# Auxillary_Supply_Break_Out.net
KiCad netlist of a schematic drawn in Altium Designer
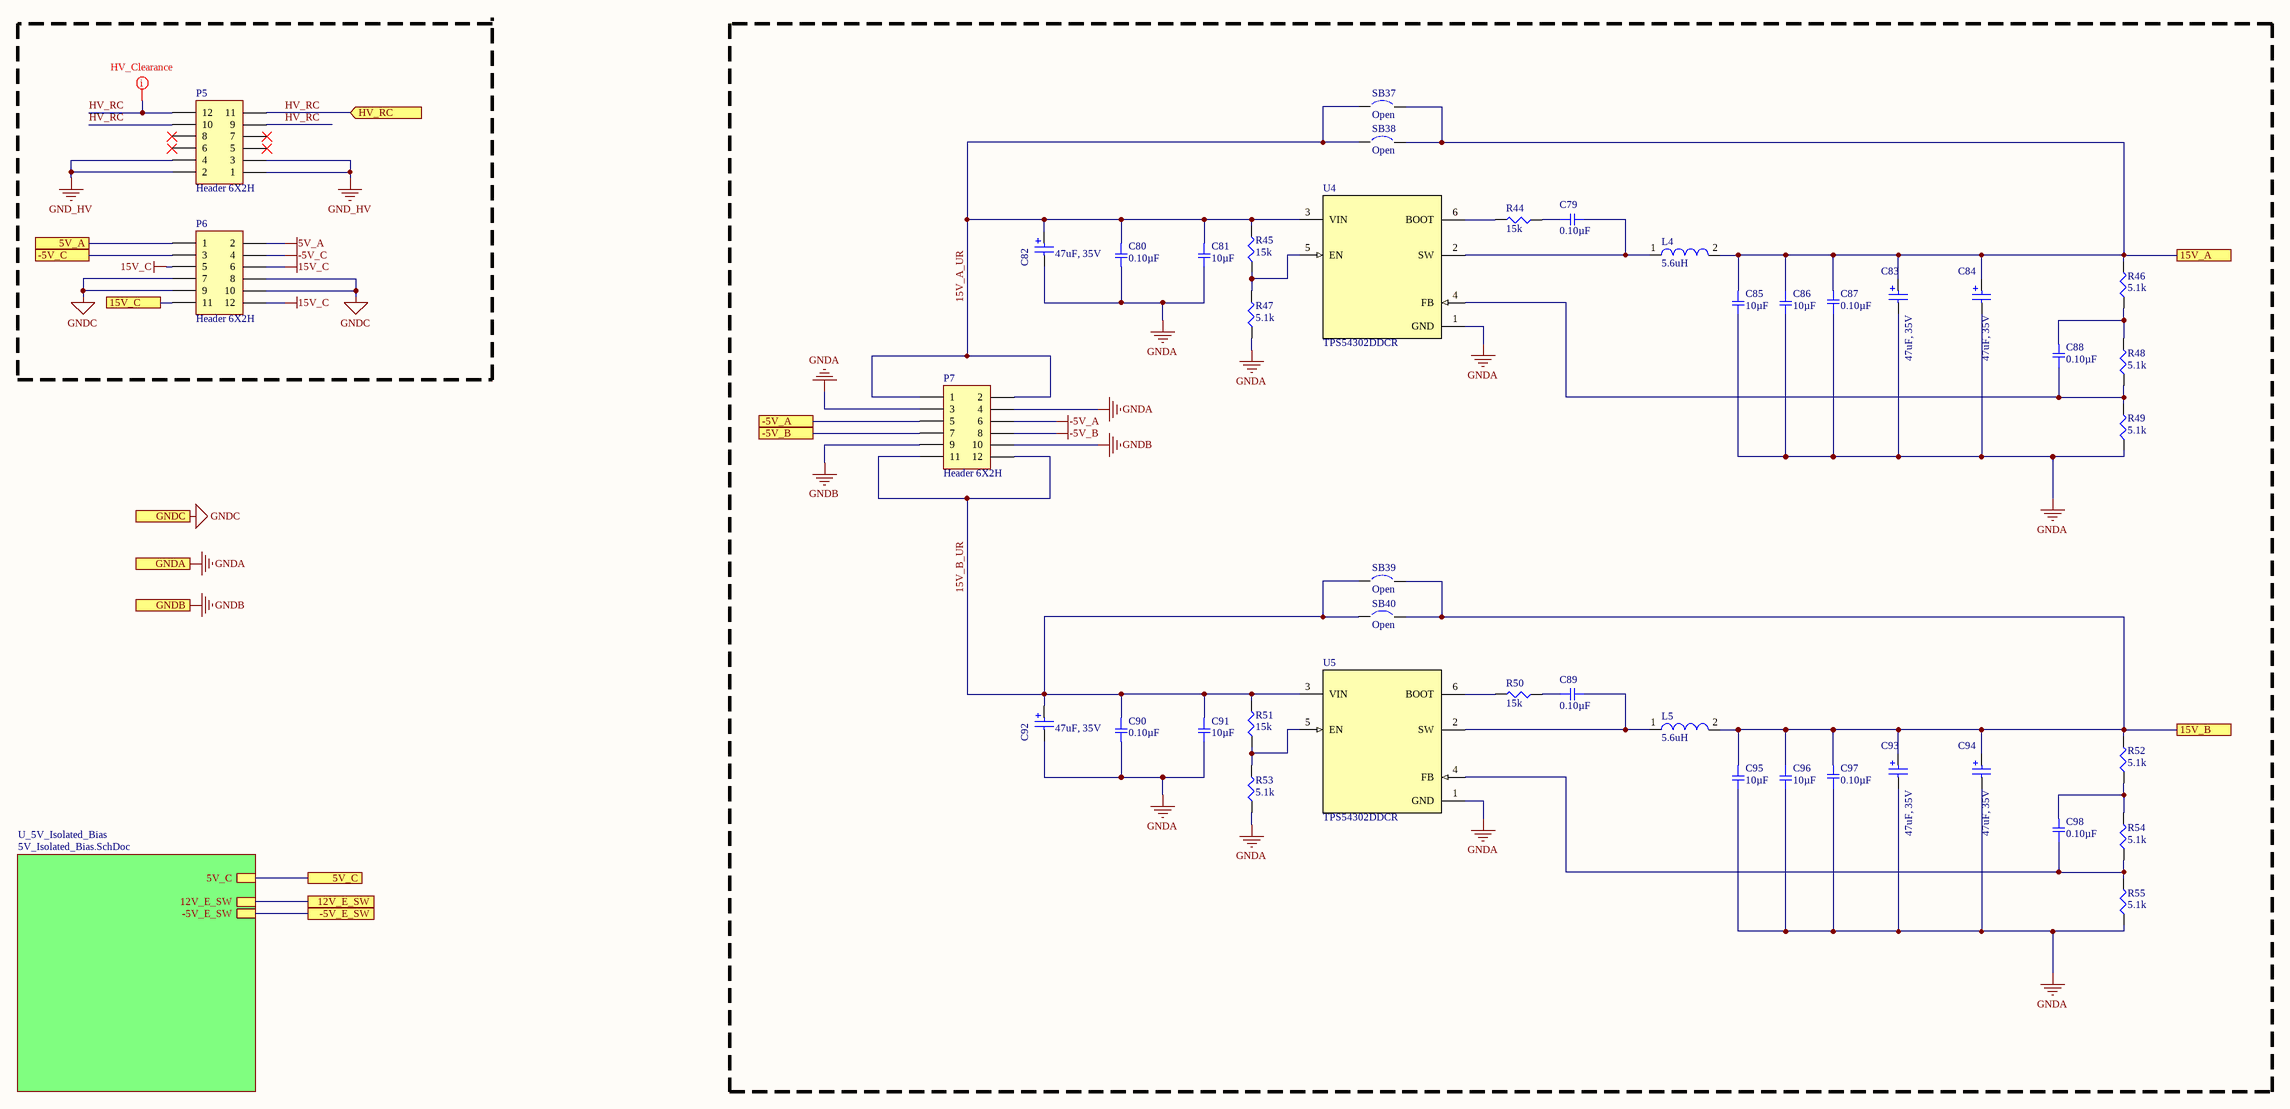
[diagram p0: Auxillary Supply Break Out.SchDoc]

(export (version "E")
  (design (tool "Eeschema 10.0.6"))
  (components
    (comp (ref "C79")
      (value "0.10µF")
      (footprint "SMD-0805C")
      (description "CAP CER 0.1UF 50V X7R 0805")
      (fields
        (field (name "DIGI-KEY PART NUMBER") "490-11955-1-ND")
        (field (name "PART NUMBER") "GCD21BR71H104KA01L")
      )
      (libsource (lib "capacitor_murata_0805") (part "GCD21BR71H104KA01L"))
    )
    (comp (ref "C80")
      (value "0.10µF")
      (footprint "SMD-0805C")
      (description "CAP CER 0.1UF 50V X7R 0805")
      (fields
        (field (name "DIGI-KEY PART NUMBER") "490-11955-1-ND")
        (field (name "PART NUMBER") "GCD21BR71H104KA01L")
      )
      (libsource (lib "capacitor_murata_0805") (part "GCD21BR71H104KA01L"))
    )
    (comp (ref "C81")
      (value "10µF")
      (footprint "SMD-0805C")
      (description "CAP CER 10UF 25V X5R 0805")
      (fields
        (field (name "DIGI-KEY PART NUMBER") "490-7207-1-ND")
        (field (name "PART NUMBER") "GRM219R61E106KA12D")
      )
      (libsource (lib "capacitor_murata_0805") (part "GRM219R61E106KA12D"))
    )
    (comp (ref "C82")
      (value "47uF, 35V")
      (footprint "WCAP-ASLU_6.3x7.7")
      (description "WCAP-ASLU Aluminium Electrolytic Capacitors, D6.3mm x L7.7mm, 47uF, +/-20%, 35VDC")
      (fields (field (name "PART NUMBER") "865090545008") (field (name "PUBLISHER") "Wurth Elektronik"))
      (libsource (lib "Altium_WCAP-ASLU_SMD") (part "865090545008"))
    )
    (comp (ref "C83")
      (value "47uF, 35V")
      (footprint "WCAP-ASLU_6.3x7.7")
      (description "WCAP-ASLU Aluminium Electrolytic Capacitors, D6.3mm x L7.7mm, 47uF, +/-20%, 35VDC")
      (fields (field (name "PART NUMBER") "865090545008") (field (name "PUBLISHER") "Wurth Elektronik"))
      (libsource (lib "Altium_WCAP-ASLU_SMD") (part "865090545008"))
    )
    (comp (ref "C84")
      (value "47uF, 35V")
      (footprint "WCAP-ASLU_6.3x7.7")
      (description "WCAP-ASLU Aluminium Electrolytic Capacitors, D6.3mm x L7.7mm, 47uF, +/-20%, 35VDC")
      (fields (field (name "PART NUMBER") "865090545008") (field (name "PUBLISHER") "Wurth Elektronik"))
      (libsource (lib "Altium_WCAP-ASLU_SMD") (part "865090545008"))
    )
    (comp (ref "C85")
      (value "10µF")
      (footprint "SMD-0805C")
      (description "CAP CER 10UF 25V X5R 0805")
      (fields
        (field (name "DIGI-KEY PART NUMBER") "490-7207-1-ND")
        (field (name "PART NUMBER") "GRM219R61E106KA12D")
      )
      (libsource (lib "capacitor_murata_0805") (part "GRM219R61E106KA12D"))
    )
    (comp (ref "C86")
      (value "10µF")
      (footprint "SMD-0805C")
      (description "CAP CER 10UF 25V X5R 0805")
      (fields
        (field (name "DIGI-KEY PART NUMBER") "490-7207-1-ND")
        (field (name "PART NUMBER") "GRM219R61E106KA12D")
      )
      (libsource (lib "capacitor_murata_0805") (part "GRM219R61E106KA12D"))
    )
    (comp (ref "C87")
      (value "0.10µF")
      (footprint "SMD-0805C")
      (description "CAP CER 0.1UF 50V X7R 0805")
      (fields
        (field (name "DIGI-KEY PART NUMBER") "490-11955-1-ND")
        (field (name "PART NUMBER") "GCD21BR71H104KA01L")
      )
      (libsource (lib "capacitor_murata_0805") (part "GCD21BR71H104KA01L"))
    )
    (comp (ref "C88")
      (value "0.10µF")
      (footprint "SMD-0805C")
      (description "CAP CER 0.1UF 50V X7R 0805")
      (fields
        (field (name "DIGI-KEY PART NUMBER") "490-11955-1-ND")
        (field (name "PART NUMBER") "GCD21BR71H104KA01L")
      )
      (libsource (lib "capacitor_murata_0805") (part "GCD21BR71H104KA01L"))
    )
    (comp (ref "C89")
      (value "0.10µF")
      (footprint "SMD-0805C")
      (description "CAP CER 0.1UF 50V X7R 0805")
      (fields
        (field (name "DIGI-KEY PART NUMBER") "490-11955-1-ND")
        (field (name "PART NUMBER") "GCD21BR71H104KA01L")
      )
      (libsource (lib "capacitor_murata_0805") (part "GCD21BR71H104KA01L"))
    )
    (comp (ref "C90")
      (value "0.10µF")
      (footprint "SMD-0805C")
      (description "CAP CER 0.1UF 50V X7R 0805")
      (fields
        (field (name "DIGI-KEY PART NUMBER") "490-11955-1-ND")
        (field (name "PART NUMBER") "GCD21BR71H104KA01L")
      )
      (libsource (lib "capacitor_murata_0805") (part "GCD21BR71H104KA01L"))
    )
    (comp (ref "C91")
      (value "10µF")
      (footprint "SMD-0805C")
      (description "CAP CER 10UF 25V X5R 0805")
      (fields
        (field (name "DIGI-KEY PART NUMBER") "490-7207-1-ND")
        (field (name "PART NUMBER") "GRM219R61E106KA12D")
      )
      (libsource (lib "capacitor_murata_0805") (part "GRM219R61E106KA12D"))
    )
    (comp (ref "C92")
      (value "47uF, 35V")
      (footprint "WCAP-ASLU_6.3x7.7")
      (description "WCAP-ASLU Aluminium Electrolytic Capacitors, D6.3mm x L7.7mm, 47uF, +/-20%, 35VDC")
      (fields (field (name "PART NUMBER") "865090545008") (field (name "PUBLISHER") "Wurth Elektronik"))
      (libsource (lib "Altium_WCAP-ASLU_SMD") (part "865090545008"))
    )
    (comp (ref "C93")
      (value "47uF, 35V")
      (footprint "WCAP-ASLU_6.3x7.7")
      (description "WCAP-ASLU Aluminium Electrolytic Capacitors, D6.3mm x L7.7mm, 47uF, +/-20%, 35VDC")
      (fields (field (name "PART NUMBER") "865090545008") (field (name "PUBLISHER") "Wurth Elektronik"))
      (libsource (lib "Altium_WCAP-ASLU_SMD") (part "865090545008"))
    )
    (comp (ref "C94")
      (value "47uF, 35V")
      (footprint "WCAP-ASLU_6.3x7.7")
      (description "WCAP-ASLU Aluminium Electrolytic Capacitors, D6.3mm x L7.7mm, 47uF, +/-20%, 35VDC")
      (fields (field (name "PART NUMBER") "865090545008") (field (name "PUBLISHER") "Wurth Elektronik"))
      (libsource (lib "Altium_WCAP-ASLU_SMD") (part "865090545008"))
    )
    (comp (ref "C95")
      (value "10µF")
      (footprint "SMD-0805C")
      (description "CAP CER 10UF 25V X5R 0805")
      (fields
        (field (name "DIGI-KEY PART NUMBER") "490-7207-1-ND")
        (field (name "PART NUMBER") "GRM219R61E106KA12D")
      )
      (libsource (lib "capacitor_murata_0805") (part "GRM219R61E106KA12D"))
    )
    (comp (ref "C96")
      (value "10µF")
      (footprint "SMD-0805C")
      (description "CAP CER 10UF 25V X5R 0805")
      (fields
        (field (name "DIGI-KEY PART NUMBER") "490-7207-1-ND")
        (field (name "PART NUMBER") "GRM219R61E106KA12D")
      )
      (libsource (lib "capacitor_murata_0805") (part "GRM219R61E106KA12D"))
    )
    (comp (ref "C97")
      (value "0.10µF")
      (footprint "SMD-0805C")
      (description "CAP CER 0.1UF 50V X7R 0805")
      (fields
        (field (name "DIGI-KEY PART NUMBER") "490-11955-1-ND")
        (field (name "PART NUMBER") "GCD21BR71H104KA01L")
      )
      (libsource (lib "capacitor_murata_0805") (part "GCD21BR71H104KA01L"))
    )
    (comp (ref "C98")
      (value "0.10µF")
      (footprint "SMD-0805C")
      (description "CAP CER 0.1UF 50V X7R 0805")
      (fields
        (field (name "DIGI-KEY PART NUMBER") "490-11955-1-ND")
        (field (name "PART NUMBER") "GCD21BR71H104KA01L")
      )
      (libsource (lib "capacitor_murata_0805") (part "GCD21BR71H104KA01L"))
    )
    (comp (ref "L4")
      (value "5.6uH")
      (footprint "WE-PD-L")
      (description "SMD-Shielded Power Inductor WE-PD, L = 4.70 µH")
      (libsource (lib "Altium Content Vault") (part "PAS-IND-INDUCTOR-2"))
    )
    (comp (ref "L5")
      (value "5.6uH")
      (footprint "WE-PD-L")
      (description "SMD-Shielded Power Inductor WE-PD, L = 4.70 µH")
      (libsource (lib "Altium Content Vault") (part "PAS-IND-INDUCTOR-2"))
    )
    (comp (ref "P5")
      (value "Header 6X2H")
      (footprint "Stackable-Conn")
      (description "Header, 6-Pin, Dual row, Right Angle")
      (fields (field (name "PUBLISHER") "Altium Limited"))
      (libsource (lib "") (part "Header 6X2H_1"))
    )
    (comp (ref "P6")
      (value "Header 6X2H")
      (footprint "Stackable-Conn")
      (description "Header, 6-Pin, Dual row, Right Angle")
      (fields (field (name "PUBLISHER") "Altium Limited"))
      (libsource (lib "Power Board UCC28951") (part "Header 6X2H"))
    )
    (comp (ref "P7")
      (value "Header 6X2H")
      (footprint "Stackable-Conn")
      (description "Header, 6-Pin, Dual row, Right Angle")
      (fields (field (name "PUBLISHER") "Altium Limited"))
      (libsource (lib "Power Board UCC28951") (part "Header 6X2H"))
    )
    (comp (ref "R44")
      (value "15k")
      (footprint "SMD-0603-RES")
      (description "RES SMD 15K OHM 1% 1/10W 0603")
      (fields
        (field (name "PART NUMBER") "ERJ-3EKF1502V")
        (field (name "DIGI-KEY PART NUMBER") "P15.0KHCT-ND")
      )
      (libsource (lib "Panasonic_ERJ_0603") (part "ERJ-3EKF1502V"))
    )
    (comp (ref "R45")
      (value "15k")
      (footprint "SMD-0603-RES")
      (description "RES SMD 15K OHM 1% 1/10W 0603")
      (fields
        (field (name "PART NUMBER") "ERJ-3EKF1502V")
        (field (name "DIGI-KEY PART NUMBER") "P15.0KHCT-ND")
      )
      (libsource (lib "Panasonic_ERJ_0603") (part "ERJ-3EKF1502V"))
    )
    (comp (ref "R46")
      (value "5.1k")
      (footprint "SMD-0603-RES")
      (description "RES SMD 5.1K OHM 1% 1/10W 0603")
      (fields
        (field (name "PART NUMBER") "ERJ-3EKF5101V")
        (field (name "DIGI-KEY PART NUMBER") "P5.10KHCT-ND")
      )
      (libsource (lib "Panasonic_ERJ_0603") (part "ERJ-3EKF5101V"))
    )
    (comp (ref "R47")
      (value "5.1k")
      (footprint "SMD-0603-RES")
      (description "RES SMD 5.1K OHM 1% 1/10W 0603")
      (fields
        (field (name "PART NUMBER") "ERJ-3EKF5101V")
        (field (name "DIGI-KEY PART NUMBER") "P5.10KHCT-ND")
      )
      (libsource (lib "Panasonic_ERJ_0603") (part "ERJ-3EKF5101V"))
    )
    (comp (ref "R48")
      (value "5.1k")
      (footprint "SMD-0603-RES")
      (description "RES SMD 5.1K OHM 1% 1/10W 0603")
      (fields
        (field (name "PART NUMBER") "ERJ-3EKF5101V")
        (field (name "DIGI-KEY PART NUMBER") "P5.10KHCT-ND")
      )
      (libsource (lib "Panasonic_ERJ_0603") (part "ERJ-3EKF5101V"))
    )
    (comp (ref "R49")
      (value "5.1k")
      (footprint "SMD-0603-RES")
      (description "RES SMD 5.1K OHM 1% 1/10W 0603")
      (fields
        (field (name "PART NUMBER") "ERJ-3EKF5101V")
        (field (name "DIGI-KEY PART NUMBER") "P5.10KHCT-ND")
      )
      (libsource (lib "Panasonic_ERJ_0603") (part "ERJ-3EKF5101V"))
    )
    (comp (ref "R50")
      (value "15k")
      (footprint "SMD-0603-RES")
      (description "RES SMD 15K OHM 1% 1/10W 0603")
      (fields
        (field (name "PART NUMBER") "ERJ-3EKF1502V")
        (field (name "DIGI-KEY PART NUMBER") "P15.0KHCT-ND")
      )
      (libsource (lib "Panasonic_ERJ_0603") (part "ERJ-3EKF1502V"))
    )
    (comp (ref "R51")
      (value "15k")
      (footprint "SMD-0603-RES")
      (description "RES SMD 15K OHM 1% 1/10W 0603")
      (fields
        (field (name "PART NUMBER") "ERJ-3EKF1502V")
        (field (name "DIGI-KEY PART NUMBER") "P15.0KHCT-ND")
      )
      (libsource (lib "Panasonic_ERJ_0603") (part "ERJ-3EKF1502V"))
    )
    (comp (ref "R52")
      (value "5.1k")
      (footprint "SMD-0603-RES")
      (description "RES SMD 5.1K OHM 1% 1/10W 0603")
      (fields
        (field (name "PART NUMBER") "ERJ-3EKF5101V")
        (field (name "DIGI-KEY PART NUMBER") "P5.10KHCT-ND")
      )
      (libsource (lib "Panasonic_ERJ_0603") (part "ERJ-3EKF5101V"))
    )
    (comp (ref "R53")
      (value "5.1k")
      (footprint "SMD-0603-RES")
      (description "RES SMD 5.1K OHM 1% 1/10W 0603")
      (fields
        (field (name "PART NUMBER") "ERJ-3EKF5101V")
        (field (name "DIGI-KEY PART NUMBER") "P5.10KHCT-ND")
      )
      (libsource (lib "Panasonic_ERJ_0603") (part "ERJ-3EKF5101V"))
    )
    (comp (ref "R54")
      (value "5.1k")
      (footprint "SMD-0603-RES")
      (description "RES SMD 5.1K OHM 1% 1/10W 0603")
      (fields
        (field (name "PART NUMBER") "ERJ-3EKF5101V")
        (field (name "DIGI-KEY PART NUMBER") "P5.10KHCT-ND")
      )
      (libsource (lib "Panasonic_ERJ_0603") (part "ERJ-3EKF5101V"))
    )
    (comp (ref "R55")
      (value "5.1k")
      (footprint "SMD-0603-RES")
      (description "RES SMD 5.1K OHM 1% 1/10W 0603")
      (fields
        (field (name "PART NUMBER") "ERJ-3EKF5101V")
        (field (name "DIGI-KEY PART NUMBER") "P5.10KHCT-ND")
      )
      (libsource (lib "Panasonic_ERJ_0603") (part "ERJ-3EKF5101V"))
    )
    (comp (ref "SB37")
      (value "Open")
      (footprint "Solder Bridge - HP")
      (description "Circuit Breaker")
      (fields (field (name "PUBLISHER") "Altium Limited"))
      (libsource (lib "Power Board UCC28951") (part "Solder Bridge"))
    )
    (comp (ref "SB38")
      (value "Open")
      (footprint "Solder Bridge - HP")
      (description "Circuit Breaker")
      (fields (field (name "PUBLISHER") "Altium Limited"))
      (libsource (lib "Power Board UCC28951") (part "Solder Bridge"))
    )
    (comp (ref "SB39")
      (value "Open")
      (footprint "Solder Bridge - HP")
      (description "Circuit Breaker")
      (fields (field (name "PUBLISHER") "Altium Limited"))
      (libsource (lib "Power Board UCC28951") (part "Solder Bridge"))
    )
    (comp (ref "SB40")
      (value "Open")
      (footprint "Solder Bridge - HP")
      (description "Circuit Breaker")
      (fields (field (name "PUBLISHER") "Altium Limited"))
      (libsource (lib "Power Board UCC28951") (part "Solder Bridge"))
    )
    (comp (ref "U4")
      (value "TPS54302DDCR")
      (footprint "SOT95P278X110-6N")
      (description "Imported")
      (fields (field (name "PARTNUMBER") "TPS54302DDC") (field (name "MANUFACTURER") "Texas Instruments"))
      (libsource (lib "Power Board UCC28951") (part "TPS54302DDCR"))
    )
    (comp (ref "U5")
      (value "TPS54302DDCR")
      (footprint "SOT95P278X110-6N")
      (description "Imported")
      (fields (field (name "PARTNUMBER") "TPS54302DDC") (field (name "MANUFACTURER") "Texas Instruments"))
      (libsource (lib "Power Board UCC28951") (part "TPS54302DDCR"))
    )
  )
  (nets
    (net (code "1") (name "-5V_A") (class "Default")
      (node (ref "P7") (pin "5") (pinfunction "5_5") (pintype "passive"))
      (node (ref "P7") (pin "6") (pinfunction "6_6") (pintype "passive"))
    )
    (net (code "2") (name "-5V_B") (class "Default")
      (node (ref "P7") (pin "7") (pinfunction "7_7") (pintype "passive"))
      (node (ref "P7") (pin "8") (pinfunction "8_8") (pintype "passive"))
    )
    (net (code "3") (name "-5V_C") (class "Default")
      (node (ref "P6") (pin "3") (pinfunction "3_3") (pintype "passive"))
      (node (ref "P6") (pin "4") (pinfunction "4_4") (pintype "passive"))
    )
    (net (code "7") (name "/15V_A") (class "Default")
      (node (ref "C83") (pin "2") (pinfunction "P_2") (pintype "passive"))
      (node (ref "C84") (pin "2") (pinfunction "P_2") (pintype "passive"))
      (node (ref "C85") (pin "1") (pinfunction "1_1") (pintype "passive"))
      (node (ref "C86") (pin "1") (pinfunction "1_1") (pintype "passive"))
      (node (ref "C87") (pin "2") (pinfunction "2_2") (pintype "passive"))
      (node (ref "L4") (pin "2") (pinfunction "2_2") (pintype "passive"))
      (node (ref "R46") (pin "2") (pinfunction "2_2") (pintype "passive"))
      (node (ref "SB37") (pin "2") (pinfunction "2_2") (pintype "passive"))
      (node (ref "SB38") (pin "2") (pinfunction "2_2") (pintype "passive"))
    )
    (net (code "8") (name "/15V_A_UR") (class "Default")
      (node (ref "C80") (pin "1") (pinfunction "1_1") (pintype "passive"))
      (node (ref "C81") (pin "1") (pinfunction "1_1") (pintype "passive"))
      (node (ref "C82") (pin "2") (pinfunction "P_2") (pintype "passive"))
      (node (ref "P7") (pin "1") (pinfunction "1_1") (pintype "passive"))
      (node (ref "P7") (pin "2") (pinfunction "2_2") (pintype "passive"))
      (node (ref "R45") (pin "2") (pinfunction "2_2") (pintype "passive"))
      (node (ref "SB37") (pin "1") (pinfunction "1_1") (pintype "passive"))
      (node (ref "SB38") (pin "1") (pinfunction "1_1") (pintype "passive"))
      (node (ref "U4") (pin "3") (pinfunction "VIN_3") (pintype "power_in"))
    )
    (net (code "9") (name "/15V_B") (class "Default")
      (node (ref "C93") (pin "2") (pinfunction "P_2") (pintype "passive"))
      (node (ref "C94") (pin "2") (pinfunction "P_2") (pintype "passive"))
      (node (ref "C95") (pin "1") (pinfunction "1_1") (pintype "passive"))
      (node (ref "C96") (pin "1") (pinfunction "1_1") (pintype "passive"))
      (node (ref "C97") (pin "2") (pinfunction "2_2") (pintype "passive"))
      (node (ref "L5") (pin "2") (pinfunction "2_2") (pintype "passive"))
      (node (ref "R52") (pin "2") (pinfunction "2_2") (pintype "passive"))
      (node (ref "SB39") (pin "2") (pinfunction "2_2") (pintype "passive"))
      (node (ref "SB40") (pin "2") (pinfunction "2_2") (pintype "passive"))
    )
    (net (code "10") (name "/15V_B_UR") (class "Default")
      (node (ref "C90") (pin "1") (pinfunction "1_1") (pintype "passive"))
      (node (ref "C91") (pin "1") (pinfunction "1_1") (pintype "passive"))
      (node (ref "C92") (pin "2") (pinfunction "P_2") (pintype "passive"))
      (node (ref "P7") (pin "11") (pinfunction "11_11") (pintype "passive"))
      (node (ref "P7") (pin "12") (pinfunction "12_12") (pintype "passive"))
      (node (ref "R51") (pin "2") (pinfunction "2_2") (pintype "passive"))
      (node (ref "SB39") (pin "1") (pinfunction "1_1") (pintype "passive"))
      (node (ref "SB40") (pin "1") (pinfunction "1_1") (pintype "passive"))
      (node (ref "U5") (pin "3") (pinfunction "VIN_3") (pintype "power_in"))
    )
    (net (code "11") (name "/HV_RC") (class "Default")
      (node (ref "P5") (pin "10") (pinfunction "10_10") (pintype "passive"))
      (node (ref "P5") (pin "11") (pinfunction "11_11") (pintype "passive"))
      (node (ref "P5") (pin "12") (pinfunction "12_12") (pintype "passive"))
      (node (ref "P5") (pin "9") (pinfunction "9_9") (pintype "passive"))
    )
    (net (code "12") (name "5V_A") (class "Default")
      (node (ref "P6") (pin "1") (pinfunction "1_1") (pintype "passive"))
      (node (ref "P6") (pin "2") (pinfunction "2_2") (pintype "passive"))
    )
    (net (code "13") (name "15V_C") (class "Default")
      (node (ref "P6") (pin "11") (pinfunction "11_11") (pintype "passive"))
      (node (ref "P6") (pin "12") (pinfunction "12_12") (pintype "passive"))
      (node (ref "P6") (pin "5") (pinfunction "5_5") (pintype "passive"))
      (node (ref "P6") (pin "6") (pinfunction "6_6") (pintype "passive"))
    )
    (net (code "14") (name "GNDA") (class "Default")
      (node (ref "C80") (pin "2") (pinfunction "2_2") (pintype "passive"))
      (node (ref "C81") (pin "2") (pinfunction "2_2") (pintype "passive"))
      (node (ref "C82") (pin "1") (pinfunction "N_1") (pintype "passive"))
      (node (ref "C83") (pin "1") (pinfunction "N_1") (pintype "passive"))
      (node (ref "C84") (pin "1") (pinfunction "N_1") (pintype "passive"))
      (node (ref "C85") (pin "2") (pinfunction "2_2") (pintype "passive"))
      (node (ref "C86") (pin "2") (pinfunction "2_2") (pintype "passive"))
      (node (ref "C87") (pin "1") (pinfunction "1_1") (pintype "passive"))
      (node (ref "C90") (pin "2") (pinfunction "2_2") (pintype "passive"))
      (node (ref "C91") (pin "2") (pinfunction "2_2") (pintype "passive"))
      (node (ref "C92") (pin "1") (pinfunction "N_1") (pintype "passive"))
      (node (ref "C93") (pin "1") (pinfunction "N_1") (pintype "passive"))
      (node (ref "C94") (pin "1") (pinfunction "N_1") (pintype "passive"))
      (node (ref "C95") (pin "2") (pinfunction "2_2") (pintype "passive"))
      (node (ref "C96") (pin "2") (pinfunction "2_2") (pintype "passive"))
      (node (ref "C97") (pin "1") (pinfunction "1_1") (pintype "passive"))
      (node (ref "P7") (pin "3") (pinfunction "3_3") (pintype "passive"))
      (node (ref "P7") (pin "4") (pinfunction "4_4") (pintype "passive"))
      (node (ref "R47") (pin "1") (pinfunction "1_1") (pintype "passive"))
      (node (ref "R49") (pin "1") (pinfunction "1_1") (pintype "passive"))
      (node (ref "R53") (pin "1") (pinfunction "1_1") (pintype "passive"))
      (node (ref "R55") (pin "1") (pinfunction "1_1") (pintype "passive"))
      (node (ref "U4") (pin "1") (pinfunction "GND_1") (pintype "power_in"))
      (node (ref "U5") (pin "1") (pinfunction "GND_1") (pintype "power_in"))
    )
    (net (code "15") (name "GNDB") (class "Default")
      (node (ref "P7") (pin "10") (pinfunction "10_10") (pintype "passive"))
      (node (ref "P7") (pin "9") (pinfunction "9_9") (pintype "passive"))
    )
    (net (code "16") (name "GNDC") (class "Default")
      (node (ref "P6") (pin "10") (pinfunction "10_10") (pintype "passive"))
      (node (ref "P6") (pin "7") (pinfunction "7_7") (pintype "passive"))
      (node (ref "P6") (pin "8") (pinfunction "8_8") (pintype "passive"))
      (node (ref "P6") (pin "9") (pinfunction "9_9") (pintype "passive"))
    )
    (net (code "17") (name "GND_HV") (class "Default")
      (node (ref "P5") (pin "1") (pinfunction "1_1") (pintype "passive"))
      (node (ref "P5") (pin "2") (pinfunction "2_2") (pintype "passive"))
      (node (ref "P5") (pin "3") (pinfunction "3_3") (pintype "passive"))
      (node (ref "P5") (pin "4") (pinfunction "4_4") (pintype "passive"))
    )
    (net (code "18") (name "Net-(C79-Pad1)") (class "Default")
      (node (ref "C79") (pin "1") (pinfunction "1_1") (pintype "passive"))
      (node (ref "R44") (pin "1") (pinfunction "1_1") (pintype "passive"))
    )
    (net (code "19") (name "Net-(C88-Pad2)") (class "Default")
      (node (ref "C88") (pin "2") (pinfunction "2_2") (pintype "passive"))
      (node (ref "R46") (pin "1") (pinfunction "1_1") (pintype "passive"))
      (node (ref "R48") (pin "2") (pinfunction "2_2") (pintype "passive"))
    )
    (net (code "20") (name "Net-(C89-Pad1)") (class "Default")
      (node (ref "C89") (pin "1") (pinfunction "1_1") (pintype "passive"))
      (node (ref "R50") (pin "1") (pinfunction "1_1") (pintype "passive"))
    )
    (net (code "21") (name "Net-(C98-Pad2)") (class "Default")
      (node (ref "C98") (pin "2") (pinfunction "2_2") (pintype "passive"))
      (node (ref "R52") (pin "1") (pinfunction "1_1") (pintype "passive"))
      (node (ref "R54") (pin "2") (pinfunction "2_2") (pintype "passive"))
    )
    (net (code "22") (name "Net-(U4-BOOT)") (class "Default")
      (node (ref "R44") (pin "2") (pinfunction "2_2") (pintype "passive"))
      (node (ref "U4") (pin "6") (pinfunction "BOOT_6") (pintype "power_in"))
    )
    (net (code "23") (name "Net-(U4-EN)") (class "Default")
      (node (ref "R45") (pin "1") (pinfunction "1_1") (pintype "passive"))
      (node (ref "R47") (pin "2") (pinfunction "2_2") (pintype "passive"))
      (node (ref "U4") (pin "5") (pinfunction "EN_5") (pintype "input"))
    )
    (net (code "24") (name "Net-(U4-FB)") (class "Default")
      (node (ref "C88") (pin "1") (pinfunction "1_1") (pintype "passive"))
      (node (ref "R48") (pin "1") (pinfunction "1_1") (pintype "passive"))
      (node (ref "R49") (pin "2") (pinfunction "2_2") (pintype "passive"))
      (node (ref "U4") (pin "4") (pinfunction "FB_4") (pintype "input"))
    )
    (net (code "25") (name "Net-(U4-SW)") (class "Default")
      (node (ref "C79") (pin "2") (pinfunction "2_2") (pintype "passive"))
      (node (ref "L4") (pin "1") (pinfunction "1_1") (pintype "passive"))
      (node (ref "U4") (pin "2") (pinfunction "SW_2") (pintype "power_in"))
    )
    (net (code "26") (name "Net-(U5-BOOT)") (class "Default")
      (node (ref "R50") (pin "2") (pinfunction "2_2") (pintype "passive"))
      (node (ref "U5") (pin "6") (pinfunction "BOOT_6") (pintype "power_in"))
    )
    (net (code "27") (name "Net-(U5-EN)") (class "Default")
      (node (ref "R51") (pin "1") (pinfunction "1_1") (pintype "passive"))
      (node (ref "R53") (pin "2") (pinfunction "2_2") (pintype "passive"))
      (node (ref "U5") (pin "5") (pinfunction "EN_5") (pintype "input"))
    )
    (net (code "28") (name "Net-(U5-FB)") (class "Default")
      (node (ref "C98") (pin "1") (pinfunction "1_1") (pintype "passive"))
      (node (ref "R54") (pin "1") (pinfunction "1_1") (pintype "passive"))
      (node (ref "R55") (pin "2") (pinfunction "2_2") (pintype "passive"))
      (node (ref "U5") (pin "4") (pinfunction "FB_4") (pintype "input"))
    )
    (net (code "29") (name "Net-(U5-SW)") (class "Default")
      (node (ref "C89") (pin "2") (pinfunction "2_2") (pintype "passive"))
      (node (ref "L5") (pin "1") (pinfunction "1_1") (pintype "passive"))
      (node (ref "U5") (pin "2") (pinfunction "SW_2") (pintype "power_in"))
    )
    (net (code "30") (name "unconnected-(P5-Pad5)") (class "Default")
      (node (ref "P5") (pin "5") (pinfunction "5_5") (pintype "passive+no_connect"))
    )
    (net (code "31") (name "unconnected-(P5-Pad6)") (class "Default")
      (node (ref "P5") (pin "6") (pinfunction "6_6") (pintype "passive+no_connect"))
    )
    (net (code "32") (name "unconnected-(P5-Pad7)") (class "Default")
      (node (ref "P5") (pin "7") (pinfunction "7_7") (pintype "passive+no_connect"))
    )
    (net (code "33") (name "unconnected-(P5-Pad8)") (class "Default")
      (node (ref "P5") (pin "8") (pinfunction "8_8") (pintype "passive+no_connect"))
    )
  )
)
